# STM32F7.net
KiCad netlist of a schematic drawn in Altium Designer
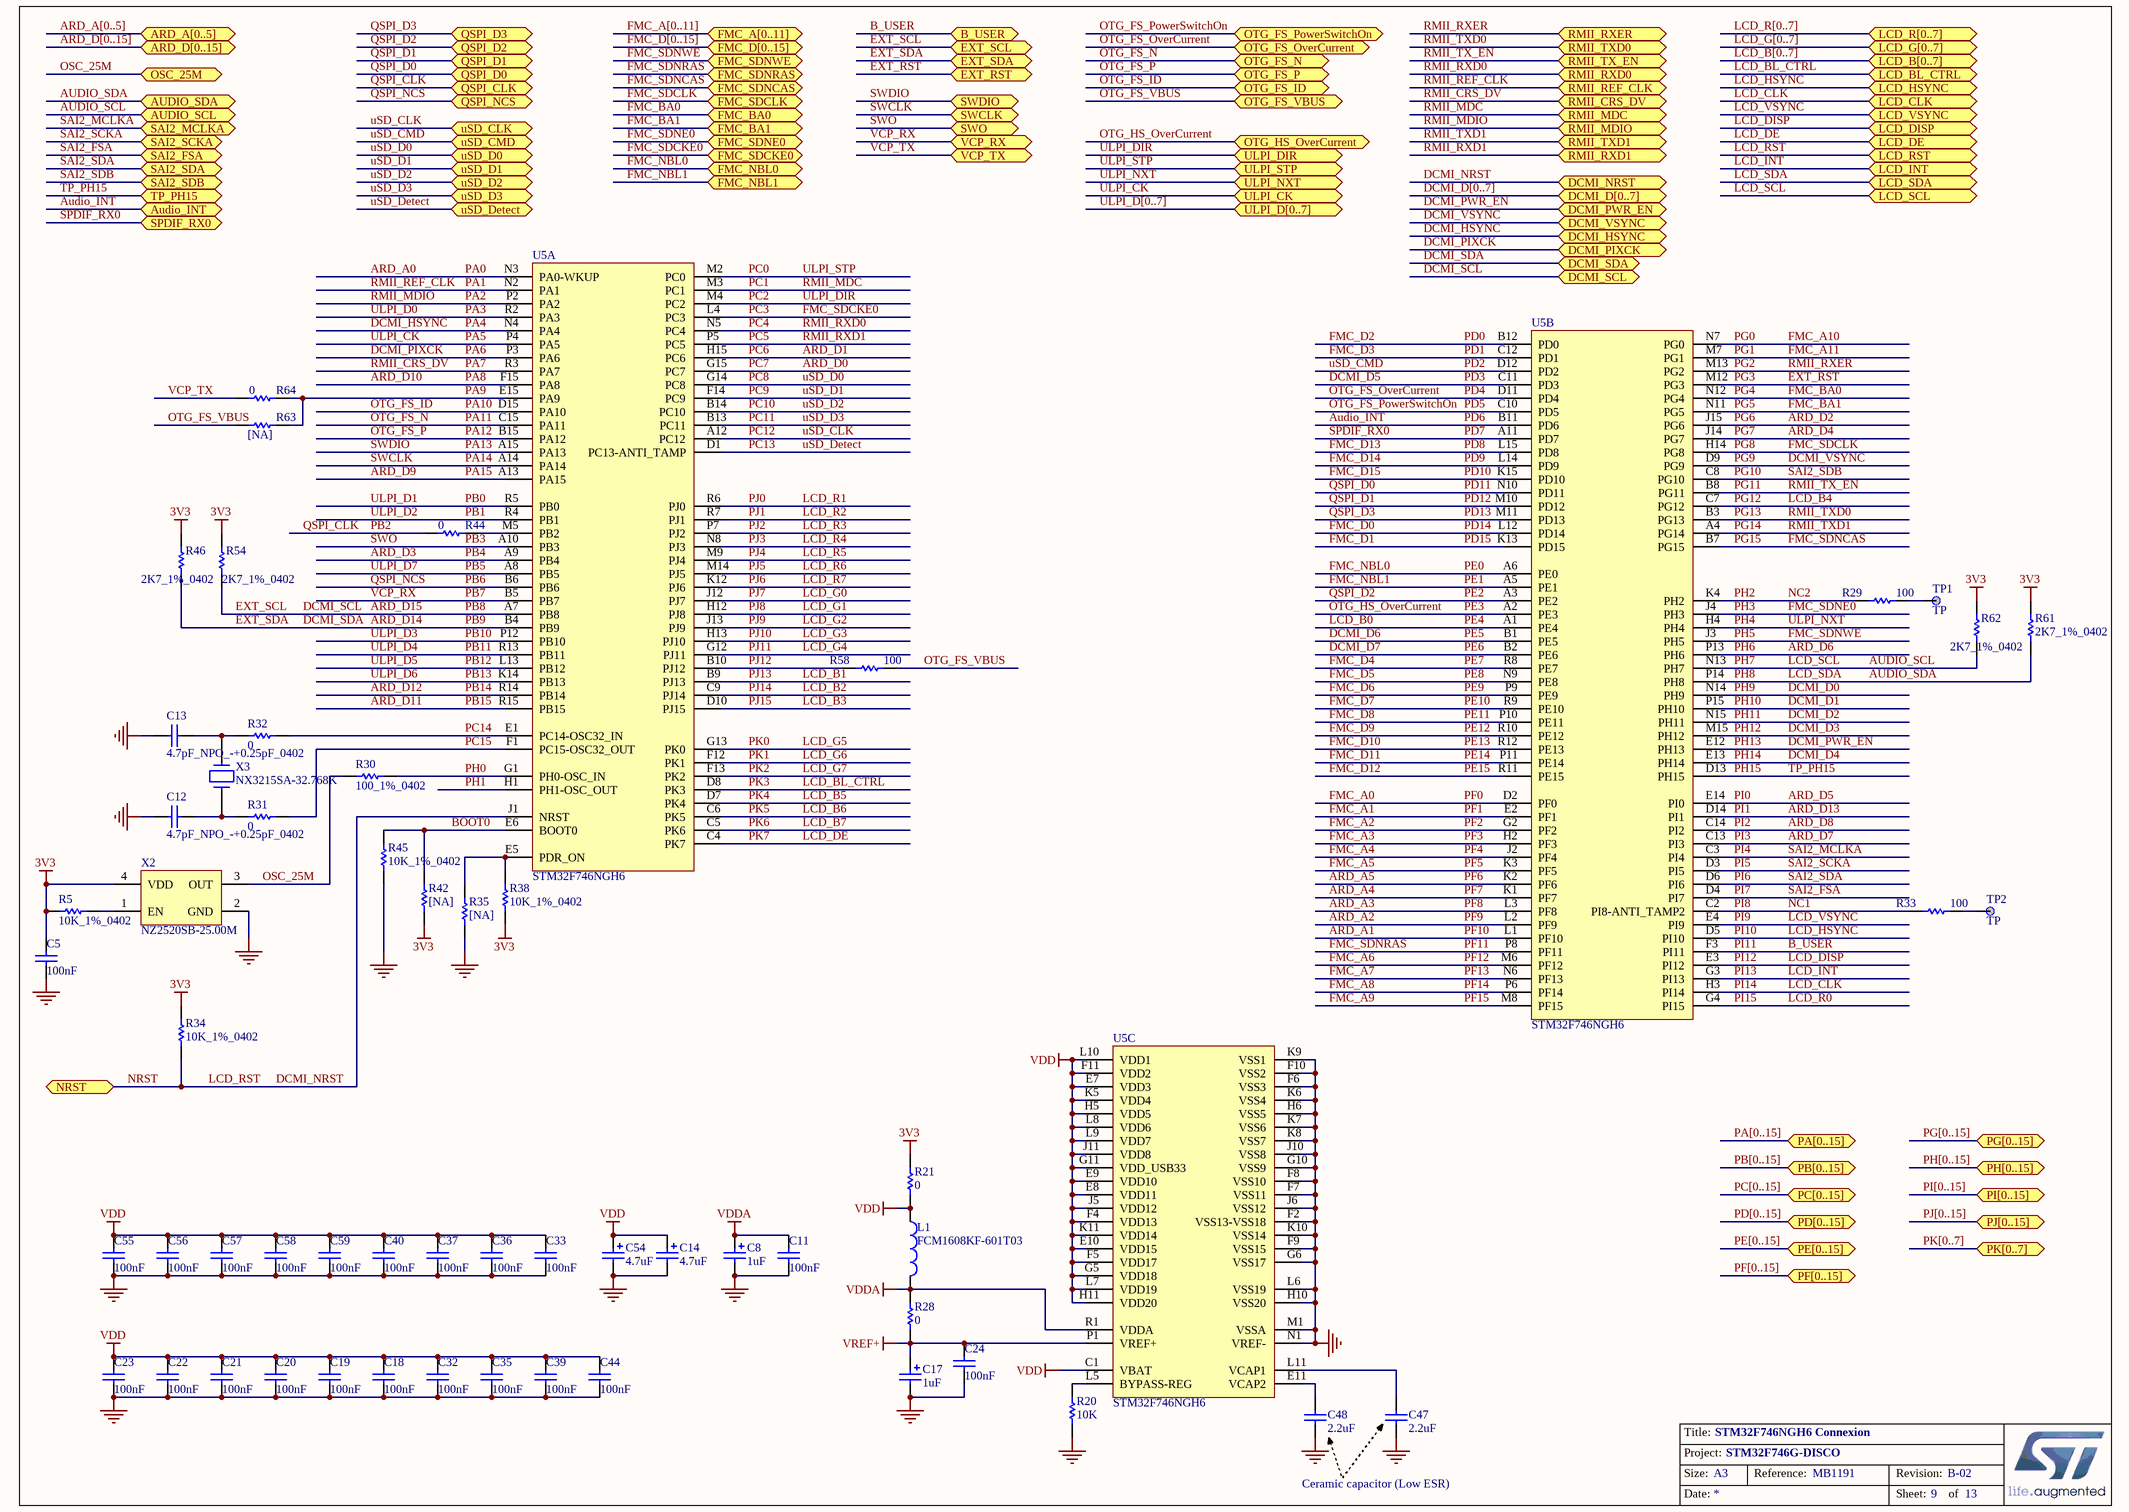
[diagram p0: STM32F7.SchDoc]

(export (version "E")
  (design (tool "Eeschema 10.0.6"))
  (components
    (comp (ref "C5")
      (value "100nF")
      (footprint "0402C")
      (description "Capacitor,100nF,16V,X7R,10%,0402,YAGEO")
      (libsource (lib "MCD_TOOLS") (part "Cap_100nF_X7R_10%_0402"))
    )
    (comp (ref "C8")
      (value "1uF")
      (footprint "TAN-A")
      (description "Polarized Capacitor,1uF,16V,10%,typeA,AVX")
      (libsource (lib "MCD_TOOLS") (part "Cap_1uF_POL_10%_TANA"))
    )
    (comp (ref "C11")
      (value "100nF")
      (footprint "0402C")
      (description "Capacitor,100nF,16V,X7R,10%,0402,YAGEO")
      (libsource (lib "MCD_TOOLS") (part "Cap_100nF_X7R_10%_0402"))
    )
    (comp (ref "C12")
      (value "4.7pF_NPO_-+0.25pF_0402")
      (footprint "0402C")
      (description "Capacitor, 4.7pF, 50V, NPO, -+0.25pF, 0402, YAGEO")
      (libsource (lib "MCD_TOOLS") (part "Cap_4.7pF_NPO_-+0.25pF_0402"))
    )
    (comp (ref "C13")
      (value "4.7pF_NPO_-+0.25pF_0402")
      (footprint "0402C")
      (description "Capacitor, 4.7pF, 50V, NPO, -+0.25pF, 0402, YAGEO")
      (libsource (lib "MCD_TOOLS") (part "Cap_4.7pF_NPO_-+0.25pF_0402"))
    )
    (comp (ref "C14")
      (value "4.7uF")
      (footprint "TAN-A")
      (description "Polarized Capacitor,4.7uF,16V,10%,typeA,AVX")
      (libsource (lib "MCD_TOOLS") (part "Cap_4.7uF_POL_10%_TANA"))
    )
    (comp (ref "C17")
      (value "1uF")
      (footprint "TAN-A")
      (description "Polarized Capacitor,1uF,16V,10%,typeA,AVX")
      (libsource (lib "MCD_TOOLS") (part "Cap_1uF_POL_10%_TANA"))
    )
    (comp (ref "C18")
      (value "100nF")
      (footprint "0402C")
      (description "Capacitor,100nF,16V,X7R,10%,0402,YAGEO")
      (libsource (lib "MCD_TOOLS") (part "Cap_100nF_X7R_10%_0402"))
    )
    (comp (ref "C19")
      (value "100nF")
      (footprint "0402C")
      (description "Capacitor,100nF,16V,X7R,10%,0402,YAGEO")
      (libsource (lib "MCD_TOOLS") (part "Cap_100nF_X7R_10%_0402"))
    )
    (comp (ref "C20")
      (value "100nF")
      (footprint "0402C")
      (description "Capacitor,100nF,16V,X7R,10%,0402,YAGEO")
      (libsource (lib "MCD_TOOLS") (part "Cap_100nF_X7R_10%_0402"))
    )
    (comp (ref "C21")
      (value "100nF")
      (footprint "0402C")
      (description "Capacitor,100nF,16V,X7R,10%,0402,YAGEO")
      (libsource (lib "MCD_TOOLS") (part "Cap_100nF_X7R_10%_0402"))
    )
    (comp (ref "C22")
      (value "100nF")
      (footprint "0402C")
      (description "Capacitor,100nF,16V,X7R,10%,0402,YAGEO")
      (libsource (lib "MCD_TOOLS") (part "Cap_100nF_X7R_10%_0402"))
    )
    (comp (ref "C23")
      (value "100nF")
      (footprint "0402C")
      (description "Capacitor,100nF,16V,X7R,10%,0402,YAGEO")
      (libsource (lib "MCD_TOOLS") (part "Cap_100nF_X7R_10%_0402"))
    )
    (comp (ref "C24")
      (value "100nF")
      (footprint "0402C")
      (description "Capacitor,100nF,16V,X7R,10%,0402,YAGEO")
      (libsource (lib "MCD_TOOLS") (part "Cap_100nF_X7R_10%_0402"))
    )
    (comp (ref "C32")
      (value "100nF")
      (footprint "0402C")
      (description "Capacitor,100nF,16V,X7R,10%,0402,YAGEO")
      (libsource (lib "MCD_TOOLS") (part "Cap_100nF_X7R_10%_0402"))
    )
    (comp (ref "C33")
      (value "100nF")
      (footprint "0402C")
      (description "Capacitor,100nF,16V,X7R,10%,0402,YAGEO")
      (libsource (lib "MCD_TOOLS") (part "Cap_100nF_X7R_10%_0402"))
    )
    (comp (ref "C35")
      (value "100nF")
      (footprint "0402C")
      (description "Capacitor,100nF,16V,X7R,10%,0402,YAGEO")
      (libsource (lib "MCD_TOOLS") (part "Cap_100nF_X7R_10%_0402"))
    )
    (comp (ref "C36")
      (value "100nF")
      (footprint "0402C")
      (description "Capacitor,100nF,16V,X7R,10%,0402,YAGEO")
      (libsource (lib "MCD_TOOLS") (part "Cap_100nF_X7R_10%_0402"))
    )
    (comp (ref "C37")
      (value "100nF")
      (footprint "0402C")
      (description "Capacitor,100nF,16V,X7R,10%,0402,YAGEO")
      (libsource (lib "MCD_TOOLS") (part "Cap_100nF_X7R_10%_0402"))
    )
    (comp (ref "C39")
      (value "100nF")
      (footprint "0402C")
      (description "Capacitor,100nF,16V,X7R,10%,0402,YAGEO")
      (libsource (lib "MCD_TOOLS") (part "Cap_100nF_X7R_10%_0402"))
    )
    (comp (ref "C40")
      (value "100nF")
      (footprint "0402C")
      (description "Capacitor,100nF,16V,X7R,10%,0402,YAGEO")
      (libsource (lib "MCD_TOOLS") (part "Cap_100nF_X7R_10%_0402"))
    )
    (comp (ref "C44")
      (value "100nF")
      (footprint "0402C")
      (description "Capacitor,100nF,16V,X7R,10%,0402,YAGEO")
      (libsource (lib "MCD_TOOLS") (part "Cap_100nF_X7R_10%_0402"))
    )
    (comp (ref "C47")
      (value "2.2uF")
      (footprint "1206C")
      (description "Capacitor,2.2uF,16V, X7R,10%,1206,YAGEO")
      (libsource (lib "MCD_TOOLS") (part "Cap_2.2uF_X7R_10%_1206"))
    )
    (comp (ref "C48")
      (value "2.2uF")
      (footprint "1206C")
      (description "Capacitor,2.2uF,16V, X7R,10%,1206,YAGEO")
      (libsource (lib "MCD_TOOLS") (part "Cap_2.2uF_X7R_10%_1206"))
    )
    (comp (ref "C54")
      (value "4.7uF")
      (footprint "TAN-A")
      (description "Polarized Capacitor,4.7uF,16V,10%,typeA,AVX")
      (libsource (lib "MCD_TOOLS") (part "Cap_4.7uF_POL_10%_TANA"))
    )
    (comp (ref "C55")
      (value "100nF")
      (footprint "0402C")
      (description "Capacitor,100nF,16V,X7R,10%,0402,YAGEO")
      (libsource (lib "MCD_TOOLS") (part "Cap_100nF_X7R_10%_0402"))
    )
    (comp (ref "C56")
      (value "100nF")
      (footprint "0402C")
      (description "Capacitor,100nF,16V,X7R,10%,0402,YAGEO")
      (libsource (lib "MCD_TOOLS") (part "Cap_100nF_X7R_10%_0402"))
    )
    (comp (ref "C57")
      (value "100nF")
      (footprint "0402C")
      (description "Capacitor,100nF,16V,X7R,10%,0402,YAGEO")
      (libsource (lib "MCD_TOOLS") (part "Cap_100nF_X7R_10%_0402"))
    )
    (comp (ref "C58")
      (value "100nF")
      (footprint "0402C")
      (description "Capacitor,100nF,16V,X7R,10%,0402,YAGEO")
      (libsource (lib "MCD_TOOLS") (part "Cap_100nF_X7R_10%_0402"))
    )
    (comp (ref "C59")
      (value "100nF")
      (footprint "0402C")
      (description "Capacitor,100nF,16V,X7R,10%,0402,YAGEO")
      (libsource (lib "MCD_TOOLS") (part "Cap_100nF_X7R_10%_0402"))
    )
    (comp (ref "L1")
      (value "FCM1608KF-601T03")
      (footprint "0603L")
      (description "Bead,600R,350mA,0603,FCM1608KF-601T03,Tai-tech")
      (libsource (lib "MCD_TOOLS") (part "BEAD_600R_350MA_0603"))
    )
    (comp (ref "R5")
      (value "10K_1%_0402")
      (footprint "0402R")
      (description "Resistor,10K,0402,1%,YAGEO")
      (libsource (lib "MCD_TOOLS") (part "Res_10K_1%_0402"))
    )
    (comp (ref "R20")
      (value "10K")
      (footprint "0402R")
      (description "Resistor,10K,0402,1%,YAGEO")
      (libsource (lib "MCD_TOOLS") (part "Res_10K_1%_0402"))
    )
    (comp (ref "R21")
      (value "0")
      (footprint "0603R-GS")
      (description "Resistor,0,0603,5%,YAGEO")
      (libsource (lib "MCD_TOOLS") (part "Res_0_5%_0603"))
    )
    (comp (ref "R28")
      (value "0")
      (footprint "0603R-GS")
      (description "Resistor,0,0603,5%,YAGEO")
      (libsource (lib "MCD_TOOLS") (part "Res_0_5%_0603"))
    )
    (comp (ref "R29")
      (value "100")
      (footprint "0402R")
      (description "Resistor,100,0402,1%,YAGEO")
      (libsource (lib "MCD_TOOLS") (part "Res_100_1%_0402"))
    )
    (comp (ref "R30")
      (value "100_1%_0402")
      (footprint "0402R")
      (description "Resistor,100,0402,1%,YAGEO")
      (libsource (lib "MCD_TOOLS") (part "Res_100_1%_0402"))
    )
    (comp (ref "R31")
      (value "0")
      (footprint "0402R")
      (description "Resistor,0,0402,5%,YAGEO")
      (libsource (lib "MCD_TOOLS") (part "Res_0_5%_0402"))
    )
    (comp (ref "R32")
      (value "0")
      (footprint "0402R")
      (description "Resistor,0,0402,5%,YAGEO")
      (libsource (lib "MCD_TOOLS") (part "Res_0_5%_0402"))
    )
    (comp (ref "R33")
      (value "100")
      (footprint "0402R")
      (description "Resistor,100,0402,1%,YAGEO")
      (libsource (lib "MCD_TOOLS") (part "Res_100_1%_0402"))
    )
    (comp (ref "R34")
      (value "10K_1%_0402")
      (footprint "0402R")
      (description "Resistor,10K,0402,1%,YAGEO")
      (libsource (lib "MCD_TOOLS") (part "Res_10K_1%_0402"))
    )
    (comp (ref "R35")
      (value "[NA]")
      (footprint "0402R")
      (description "Resistor,[NA],0402")
      (libsource (lib "MCD_TOOLS") (part "Res_NA_0402"))
    )
    (comp (ref "R38")
      (value "10K_1%_0402")
      (footprint "0402R")
      (description "Resistor,10K,0402,1%,YAGEO")
      (libsource (lib "MCD_TOOLS") (part "Res_10K_1%_0402"))
    )
    (comp (ref "R42")
      (value "[NA]")
      (footprint "0402R")
      (description "Resistor,[NA],0402")
      (libsource (lib "MCD_TOOLS") (part "Res_NA_0402"))
    )
    (comp (ref "R44")
      (value "0")
      (footprint "0402R")
      (description "Resistor,0,0402,5%,YAGEO")
      (libsource (lib "MCD_TOOLS") (part "Res_0_5%_0402"))
    )
    (comp (ref "R45")
      (value "10K_1%_0402")
      (footprint "0402R")
      (description "Resistor,10K,0402,1%,YAGEO")
      (libsource (lib "MCD_TOOLS") (part "Res_10K_1%_0402"))
    )
    (comp (ref "R46")
      (value "2K7_1%_0402")
      (footprint "0402R")
      (description "Resistor,2K7,0402,1%,YAGEO")
      (libsource (lib "MCD_TOOLS") (part "Res_2K7_1%_0402"))
    )
    (comp (ref "R54")
      (value "2K7_1%_0402")
      (footprint "0402R")
      (description "Resistor,2K7,0402,1%,YAGEO")
      (libsource (lib "MCD_TOOLS") (part "Res_2K7_1%_0402"))
    )
    (comp (ref "R58")
      (value "100")
      (footprint "0402R")
      (description "Resistor,100,0402,1%,YAGEO")
      (libsource (lib "MCD_TOOLS") (part "Res_100_1%_0402"))
    )
    (comp (ref "R61")
      (value "2K7_1%_0402")
      (footprint "0402R")
      (description "Resistor,2K7,0402,1%,YAGEO")
      (libsource (lib "MCD_TOOLS") (part "Res_2K7_1%_0402"))
    )
    (comp (ref "R62")
      (value "2K7_1%_0402")
      (footprint "0402R")
      (description "Resistor,2K7,0402,1%,YAGEO")
      (libsource (lib "MCD_TOOLS") (part "Res_2K7_1%_0402"))
    )
    (comp (ref "R63")
      (value "[NA]")
      (footprint "0402R")
      (description "Resistor,[NA],0402")
      (libsource (lib "MCD_TOOLS") (part "Res_NA_0402"))
    )
    (comp (ref "R64")
      (value "0")
      (footprint "0402R")
      (description "Resistor,0,0402,5%,YAGEO")
      (libsource (lib "MCD_TOOLS") (part "Res_0_5%_0402"))
    )
    (comp (ref "TP1")
      (value "TP")
      (footprint "SMDTEST-1MM")
      (description "Test Point CMS")
      (libsource (lib "MCD_TOOLS") (part "TP"))
    )
    (comp (ref "TP2")
      (value "TP")
      (footprint "SMDTEST-1MM")
      (description "Test Point CMS")
      (libsource (lib "MCD_TOOLS") (part "TP"))
    )
    (comp (ref "U5")
      (value "STM32F746NGH6")
      (footprint "BGA216_0R8_13X13_SKT")
      (description "STM32F746NGH6 (STM32F7 Birdie) TBGA216")
      (libsource (lib "MCD_TOOLS") (part "STM32F746NGH6U"))
    )
    (comp (ref "X2")
      (value "NZ2520SB-25.00M")
      (footprint "OSC_4SM_2R5X2R0")
      (description "Oscillator 25.00Mhz, -+50PPM, 3.3V, Temp -55 to +125°C")
      (libsource (lib "MCD_TOOLS") (part "OSC_25M_NZ2520SB"))
    )
    (comp (ref "X3")
      (value "NX3215SA-32.768K")
      (footprint "XTAL_2SM_3R2X1R5")
      (description "Crystal 32.768kHz, 6pF, -+20PPM, NDK only for ST, Type NX3215SA,  NDK Spec EXS00A-MU00525")
      (libsource (lib "MCD_TOOLS") (part "XTAL_32K_NX3215SA"))
    )
  )
  (nets
    (net (code "1") (name "/ARD_A0") (class "Default")
      (node (ref "U5") (pin "N3") (pinfunction "PA0-WKUP_N3") (pintype "passive"))
    )
    (net (code "2") (name "/ARD_A1") (class "Default")
      (node (ref "U5") (pin "L1") (pinfunction "PF10_L1") (pintype "passive"))
    )
    (net (code "3") (name "/ARD_A2") (class "Default")
      (node (ref "U5") (pin "L2") (pinfunction "PF9_L2") (pintype "passive"))
    )
    (net (code "4") (name "/ARD_A3") (class "Default")
      (node (ref "U5") (pin "L3") (pinfunction "PF8_L3") (pintype "passive"))
    )
    (net (code "5") (name "/ARD_A4") (class "Default")
      (node (ref "U5") (pin "K1") (pinfunction "PF7_K1") (pintype "passive"))
    )
    (net (code "6") (name "/ARD_A5") (class "Default")
      (node (ref "U5") (pin "K2") (pinfunction "PF6_K2") (pintype "passive"))
    )
    (net (code "8") (name "/ARD_D0") (class "Default")
      (node (ref "U5") (pin "G15") (pinfunction "PC7_G15") (pintype "passive"))
    )
    (net (code "9") (name "/ARD_D1") (class "Default")
      (node (ref "U5") (pin "H15") (pinfunction "PC6_H15") (pintype "passive"))
    )
    (net (code "10") (name "/ARD_D2") (class "Default")
      (node (ref "U5") (pin "J15") (pinfunction "PG6_J15") (pintype "passive"))
    )
    (net (code "11") (name "/ARD_D3") (class "Default")
      (node (ref "U5") (pin "A9") (pinfunction "PB4_A9") (pintype "passive"))
    )
    (net (code "12") (name "/ARD_D4") (class "Default")
      (node (ref "U5") (pin "J14") (pinfunction "PG7_J14") (pintype "passive"))
    )
    (net (code "13") (name "/ARD_D5") (class "Default")
      (node (ref "U5") (pin "E14") (pinfunction "PI0_E14") (pintype "passive"))
    )
    (net (code "14") (name "/ARD_D6") (class "Default")
      (node (ref "U5") (pin "P13") (pinfunction "PH6_P13") (pintype "passive"))
    )
    (net (code "15") (name "/ARD_D7") (class "Default")
      (node (ref "U5") (pin "C13") (pinfunction "PI3_C13") (pintype "passive"))
    )
    (net (code "16") (name "/ARD_D8") (class "Default")
      (node (ref "U5") (pin "C14") (pinfunction "PI2_C14") (pintype "passive"))
    )
    (net (code "17") (name "/ARD_D9") (class "Default")
      (node (ref "U5") (pin "A13") (pinfunction "PA15_A13") (pintype "passive"))
    )
    (net (code "18") (name "/ARD_D10") (class "Default")
      (node (ref "U5") (pin "F15") (pinfunction "PA8_F15") (pintype "passive"))
    )
    (net (code "19") (name "/ARD_D11") (class "Default")
      (node (ref "U5") (pin "R15") (pinfunction "PB15_R15") (pintype "passive"))
    )
    (net (code "20") (name "/ARD_D12") (class "Default")
      (node (ref "U5") (pin "R14") (pinfunction "PB14_R14") (pintype "passive"))
    )
    (net (code "21") (name "/ARD_D13") (class "Default")
      (node (ref "U5") (pin "D14") (pinfunction "PI1_D14") (pintype "passive"))
    )
    (net (code "22") (name "/ARD_D14") (class "Default")
      (node (ref "R46") (pin "1") (pinfunction "1_1") (pintype "passive"))
      (node (ref "U5") (pin "B4") (pinfunction "PB9_B4") (pintype "passive"))
    )
    (net (code "23") (name "/ARD_D15") (class "Default")
      (node (ref "R54") (pin "1") (pinfunction "1_1") (pintype "passive"))
      (node (ref "U5") (pin "A7") (pinfunction "PB8_A7") (pintype "passive"))
    )
    (net (code "25") (name "/BOOT0") (class "Default")
      (node (ref "R42") (pin "2") (pinfunction "2_2") (pintype "passive"))
      (node (ref "R45") (pin "2") (pinfunction "2_2") (pintype "passive"))
      (node (ref "U5") (pin "E6") (pinfunction "BOOT0_E6") (pintype "passive"))
    )
    (net (code "26") (name "/DCMI_D0") (class "Default")
      (node (ref "U5") (pin "N14") (pinfunction "PH9_N14") (pintype "passive"))
    )
    (net (code "27") (name "/DCMI_D1") (class "Default")
      (node (ref "U5") (pin "P15") (pinfunction "PH10_P15") (pintype "passive"))
    )
    (net (code "28") (name "/DCMI_D2") (class "Default")
      (node (ref "U5") (pin "N15") (pinfunction "PH11_N15") (pintype "passive"))
    )
    (net (code "29") (name "/DCMI_D3") (class "Default")
      (node (ref "U5") (pin "M15") (pinfunction "PH12_M15") (pintype "passive"))
    )
    (net (code "30") (name "/DCMI_D4") (class "Default")
      (node (ref "U5") (pin "E13") (pinfunction "PH14_E13") (pintype "passive"))
    )
    (net (code "31") (name "/DCMI_D5") (class "Default")
      (node (ref "U5") (pin "C11") (pinfunction "PD3_C11") (pintype "passive"))
    )
    (net (code "32") (name "/DCMI_D6") (class "Default")
      (node (ref "U5") (pin "B1") (pinfunction "PE5_B1") (pintype "passive"))
    )
    (net (code "33") (name "/DCMI_D7") (class "Default")
      (node (ref "U5") (pin "B2") (pinfunction "PE6_B2") (pintype "passive"))
    )
    (net (code "35") (name "/DCMI_NRST") (class "Default")
      (node (ref "R34") (pin "1") (pinfunction "1_1") (pintype "passive"))
      (node (ref "U5") (pin "J1") (pinfunction "NRST_J1") (pintype "passive"))
    )
    (net (code "36") (name "/FMC_A0") (class "Default")
      (node (ref "U5") (pin "D2") (pinfunction "PF0_D2") (pintype "passive"))
    )
    (net (code "37") (name "/FMC_A1") (class "Default")
      (node (ref "U5") (pin "E2") (pinfunction "PF1_E2") (pintype "passive"))
    )
    (net (code "38") (name "/FMC_A2") (class "Default")
      (node (ref "U5") (pin "G2") (pinfunction "PF2_G2") (pintype "passive"))
    )
    (net (code "39") (name "/FMC_A3") (class "Default")
      (node (ref "U5") (pin "H2") (pinfunction "PF3_H2") (pintype "passive"))
    )
    (net (code "40") (name "/FMC_A4") (class "Default")
      (node (ref "U5") (pin "J2") (pinfunction "PF4_J2") (pintype "passive"))
    )
    (net (code "41") (name "/FMC_A5") (class "Default")
      (node (ref "U5") (pin "K3") (pinfunction "PF5_K3") (pintype "passive"))
    )
    (net (code "42") (name "/FMC_A6") (class "Default")
      (node (ref "U5") (pin "M6") (pinfunction "PF12_M6") (pintype "passive"))
    )
    (net (code "43") (name "/FMC_A7") (class "Default")
      (node (ref "U5") (pin "N6") (pinfunction "PF13_N6") (pintype "passive"))
    )
    (net (code "44") (name "/FMC_A8") (class "Default")
      (node (ref "U5") (pin "P6") (pinfunction "PF14_P6") (pintype "passive"))
    )
    (net (code "45") (name "/FMC_A9") (class "Default")
      (node (ref "U5") (pin "M8") (pinfunction "PF15_M8") (pintype "passive"))
    )
    (net (code "46") (name "/FMC_A10") (class "Default")
      (node (ref "U5") (pin "N7") (pinfunction "PG0_N7") (pintype "passive"))
    )
    (net (code "47") (name "/FMC_A11") (class "Default")
      (node (ref "U5") (pin "M7") (pinfunction "PG1_M7") (pintype "passive"))
    )
    (net (code "49") (name "/FMC_D0") (class "Default")
      (node (ref "U5") (pin "L12") (pinfunction "PD14_L12") (pintype "passive"))
    )
    (net (code "50") (name "/FMC_D1") (class "Default")
      (node (ref "U5") (pin "K13") (pinfunction "PD15_K13") (pintype "passive"))
    )
    (net (code "51") (name "/FMC_D2") (class "Default")
      (node (ref "U5") (pin "B12") (pinfunction "PD0_B12") (pintype "passive"))
    )
    (net (code "52") (name "/FMC_D3") (class "Default")
      (node (ref "U5") (pin "C12") (pinfunction "PD1_C12") (pintype "passive"))
    )
    (net (code "53") (name "/FMC_D4") (class "Default")
      (node (ref "U5") (pin "R8") (pinfunction "PE7_R8") (pintype "passive"))
    )
    (net (code "54") (name "/FMC_D5") (class "Default")
      (node (ref "U5") (pin "N9") (pinfunction "PE8_N9") (pintype "passive"))
    )
    (net (code "55") (name "/FMC_D6") (class "Default")
      (node (ref "U5") (pin "P9") (pinfunction "PE9_P9") (pintype "passive"))
    )
    (net (code "56") (name "/FMC_D7") (class "Default")
      (node (ref "U5") (pin "R9") (pinfunction "PE10_R9") (pintype "passive"))
    )
    (net (code "57") (name "/FMC_D8") (class "Default")
      (node (ref "U5") (pin "P10") (pinfunction "PE11_P10") (pintype "passive"))
    )
    (net (code "58") (name "/FMC_D9") (class "Default")
      (node (ref "U5") (pin "R10") (pinfunction "PE12_R10") (pintype "passive"))
    )
    (net (code "59") (name "/FMC_D10") (class "Default")
      (node (ref "U5") (pin "R12") (pinfunction "PE13_R12") (pintype "passive"))
    )
    (net (code "60") (name "/FMC_D11") (class "Default")
      (node (ref "U5") (pin "P11") (pinfunction "PE14_P11") (pintype "passive"))
    )
    (net (code "61") (name "/FMC_D12") (class "Default")
      (node (ref "U5") (pin "R11") (pinfunction "PE15_R11") (pintype "passive"))
    )
    (net (code "62") (name "/FMC_D13") (class "Default")
      (node (ref "U5") (pin "L15") (pinfunction "PD8_L15") (pintype "passive"))
    )
    (net (code "63") (name "/FMC_D14") (class "Default")
      (node (ref "U5") (pin "L14") (pinfunction "PD9_L14") (pintype "passive"))
    )
    (net (code "64") (name "/FMC_D15") (class "Default")
      (node (ref "U5") (pin "K15") (pinfunction "PD10_K15") (pintype "passive"))
    )
    (net (code "66") (name "/LCD_B0") (class "Default")
      (node (ref "U5") (pin "A1") (pinfunction "PE4_A1") (pintype "passive"))
    )
    (net (code "67") (name "/LCD_B1") (class "Default")
      (node (ref "U5") (pin "B9") (pinfunction "PJ13_B9") (pintype "passive"))
    )
    (net (code "68") (name "/LCD_B2") (class "Default")
      (node (ref "U5") (pin "C9") (pinfunction "PJ14_C9") (pintype "passive"))
    )
    (net (code "69") (name "/LCD_B3") (class "Default")
      (node (ref "U5") (pin "D10") (pinfunction "PJ15_D10") (pintype "passive"))
    )
    (net (code "70") (name "/LCD_B4") (class "Default")
      (node (ref "U5") (pin "C7") (pinfunction "PG12_C7") (pintype "passive"))
    )
    (net (code "71") (name "/LCD_B5") (class "Default")
      (node (ref "U5") (pin "D7") (pinfunction "PK4_D7") (pintype "passive"))
    )
    (net (code "72") (name "/LCD_B6") (class "Default")
      (node (ref "U5") (pin "C6") (pinfunction "PK5_C6") (pintype "passive"))
    )
    (net (code "73") (name "/LCD_B7") (class "Default")
      (node (ref "U5") (pin "C5") (pinfunction "PK6_C5") (pintype "passive"))
    )
    (net (code "75") (name "/LCD_G0") (class "Default")
      (node (ref "U5") (pin "J12") (pinfunction "PJ7_J12") (pintype "passive"))
    )
    (net (code "76") (name "/LCD_G1") (class "Default")
      (node (ref "U5") (pin "H12") (pinfunction "PJ8_H12") (pintype "passive"))
    )
    (net (code "77") (name "/LCD_G2") (class "Default")
      (node (ref "U5") (pin "J13") (pinfunction "PJ9_J13") (pintype "passive"))
    )
    (net (code "78") (name "/LCD_G3") (class "Default")
      (node (ref "U5") (pin "H13") (pinfunction "PJ10_H13") (pintype "passive"))
    )
    (net (code "79") (name "/LCD_G4") (class "Default")
      (node (ref "U5") (pin "G12") (pinfunction "PJ11_G12") (pintype "passive"))
    )
    (net (code "80") (name "/LCD_G5") (class "Default")
      (node (ref "U5") (pin "G13") (pinfunction "PK0_G13") (pintype "passive"))
    )
    (net (code "81") (name "/LCD_G6") (class "Default")
      (node (ref "U5") (pin "F12") (pinfunction "PK1_F12") (pintype "passive"))
    )
    (net (code "82") (name "/LCD_G7") (class "Default")
      (node (ref "U5") (pin "F13") (pinfunction "PK2_F13") (pintype "passive"))
    )
    (net (code "84") (name "/LCD_R0") (class "Default")
      (node (ref "U5") (pin "G4") (pinfunction "PI15_G4") (pintype "passive"))
    )
    (net (code "85") (name "/LCD_R1") (class "Default")
      (node (ref "U5") (pin "R6") (pinfunction "PJ0_R6") (pintype "passive"))
    )
    (net (code "86") (name "/LCD_R2") (class "Default")
      (node (ref "U5") (pin "R7") (pinfunction "PJ1_R7") (pintype "passive"))
    )
    (net (code "87") (name "/LCD_R3") (class "Default")
      (node (ref "U5") (pin "P7") (pinfunction "PJ2_P7") (pintype "passive"))
    )
    (net (code "88") (name "/LCD_R4") (class "Default")
      (node (ref "U5") (pin "N8") (pinfunction "PJ3_N8") (pintype "passive"))
    )
    (net (code "89") (name "/LCD_R5") (class "Default")
      (node (ref "U5") (pin "M9") (pinfunction "PJ4_M9") (pintype "passive"))
    )
    (net (code "90") (name "/LCD_R6") (class "Default")
      (node (ref "U5") (pin "M14") (pinfunction "PJ5_M14") (pintype "passive"))
    )
    (net (code "91") (name "/LCD_R7") (class "Default")
      (node (ref "U5") (pin "K12") (pinfunction "PJ6_K12") (pintype "passive"))
    )
    (net (code "93") (name "/OSC_25M") (class "Default")
      (node (ref "R30") (pin "1") (pinfunction "1_1") (pintype "passive"))
      (node (ref "X2") (pin "3") (pinfunction "OUT_3") (pintype "passive"))
    )
    (net (code "94") (name "/OTG_FS_VBUS") (class "Default")
      (node (ref "R58") (pin "2") (pinfunction "2_2") (pintype "passive"))
      (node (ref "R63") (pin "1") (pinfunction "1_1") (pintype "passive"))
    )
    (net (code "95") (name "/PA1") (class "Default")
      (node (ref "U5") (pin "N2") (pinfunction "PA1_N2") (pintype "passive"))
    )
    (net (code "96") (name "/PA2") (class "Default")
      (node (ref "U5") (pin "P2") (pinfunction "PA2_P2") (pintype "passive"))
    )
    (net (code "97") (name "/PA4") (class "Default")
      (node (ref "U5") (pin "N4") (pinfunction "PA4_N4") (pintype "passive"))
    )
    (net (code "98") (name "/PA5") (class "Default")
      (node (ref "U5") (pin "P4") (pinfunction "PA5_P4") (pintype "passive"))
    )
    (net (code "99") (name "/PA6") (class "Default")
      (node (ref "U5") (pin "P3") (pinfunction "PA6_P3") (pintype "passive"))
    )
    (net (code "100") (name "/PA7") (class "Default")
      (node (ref "U5") (pin "R3") (pinfunction "PA7_R3") (pintype "passive"))
    )
    (net (code "101") (name "/PA9") (class "Default")
      (node (ref "R63") (pin "2") (pinfunction "2_2") (pintype "passive"))
      (node (ref "R64") (pin "2") (pinfunction "2_2") (pintype "passive"))
      (node (ref "U5") (pin "E15") (pinfunction "PA9_E15") (pintype "passive"))
    )
    (net (code "102") (name "/PA10") (class "Default")
      (node (ref "U5") (pin "D15") (pinfunction "PA10_D15") (pintype "passive"))
    )
    (net (code "103") (name "/PA11") (class "Default")
      (node (ref "U5") (pin "C15") (pinfunction "PA11_C15") (pintype "passive"))
    )
    (net (code "104") (name "/PA12") (class "Default")
      (node (ref "U5") (pin "B15") (pinfunction "PA12_B15") (pintype "passive"))
    )
    (net (code "105") (name "/PA13") (class "Default")
      (node (ref "U5") (pin "A15") (pinfunction "PA13_A15") (pintype "passive"))
    )
    (net (code "106") (name "/PA14") (class "Default")
      (node (ref "U5") (pin "A14") (pinfunction "PA14_A14") (pintype "passive"))
    )
    (net (code "108") (name "/PB2") (class "Default")
      (node (ref "R44") (pin "1") (pinfunction "1_1") (pintype "passive"))
    )
    (net (code "109") (name "/PB3") (class "Default")
      (node (ref "U5") (pin "A10") (pinfunction "PB3_A10") (pintype "passive"))
    )
    (net (code "110") (name "/PB6") (class "Default")
      (node (ref "U5") (pin "B6") (pinfunction "PB6_B6") (pintype "passive"))
    )
    (net (code "111") (name "/PB7") (class "Default")
      (node (ref "U5") (pin "B5") (pinfunction "PB7_B5") (pintype "passive"))
    )
    (net (code "113") (name "/PC0") (class "Default")
      (node (ref "U5") (pin "M2") (pinfunction "PC0_M2") (pintype "passive"))
    )
    (net (code "114") (name "/PC1") (class "Default")
      (node (ref "U5") (pin "M3") (pinfunction "PC1_M3") (pintype "passive"))
    )
    (net (code "115") (name "/PC2") (class "Default")
      (node (ref "U5") (pin "M4") (pinfunction "PC2_M4") (pintype "passive"))
    )
    (net (code "116") (name "/PC3") (class "Default")
      (node (ref "U5") (pin "L4") (pinfunction "PC3_L4") (pintype "passive"))
    )
    (net (code "117") (name "/PC4") (class "Default")
      (node (ref "U5") (pin "N5") (pinfunction "PC4_N5") (pintype "passive"))
    )
    (net (code "118") (name "/PC5") (class "Default")
      (node (ref "U5") (pin "P5") (pinfunction "PC5_P5") (pintype "passive"))
    )
    (net (code "119") (name "/PC8") (class "Default")
      (node (ref "U5") (pin "G14") (pinfunction "PC8_G14") (pintype "passive"))
    )
    (net (code "120") (name "/PC9") (class "Default")
      (node (ref "U5") (pin "F14") (pinfunction "PC9_F14") (pintype "passive"))
    )
    (net (code "121") (name "/PC10") (class "Default")
      (node (ref "U5") (pin "B14") (pinfunction "PC10_B14") (pintype "passive"))
    )
    (net (code "122") (name "/PC11") (class "Default")
      (node (ref "U5") (pin "B13") (pinfunction "PC11_B13") (pintype "passive"))
    )
    (net (code "123") (name "/PC12") (class "Default")
      (node (ref "U5") (pin "A12") (pinfunction "PC12_A12") (pintype "passive"))
    )
    (net (code "124") (name "/PC13") (class "Default")
      (node (ref "U5") (pin "D1") (pinfunction "PC13-ANTI_TAMP_D1") (pintype "passive"))
    )
    (net (code "125") (name "/PC14") (class "Default")
      (node (ref "R32") (pin "2") (pinfunction "2_2") (pintype "passive"))
      (node (ref "U5") (pin "E1") (pinfunction "PC14-OSC32_IN_E1") (pintype "passive"))
    )
    (net (code "126") (name "/PC15") (class "Default")
      (node (ref "R31") (pin "2") (pinfunction "2_2") (pintype "passive"))
      (node (ref "U5") (pin "F1") (pinfunction "PC15-OSC32_OUT_F1") (pintype "passive"))
    )
    (net (code "128") (name "/PD2") (class "Default")
      (node (ref "U5") (pin "D12") (pinfunction "PD2_D12") (pintype "passive"))
    )
    (net (code "129") (name "/PD4") (class "Default")
      (node (ref "U5") (pin "D11") (pinfunction "PD4_D11") (pintype "passive"))
    )
    (net (code "130") (name "/PD5") (class "Default")
      (node (ref "U5") (pin "C10") (pinfunction "PD5_C10") (pintype "passive"))
    )
    (net (code "131") (name "/PD6") (class "Default")
      (node (ref "U5") (pin "B11") (pinfunction "PD6_B11") (pintype "passive"))
    )
    (net (code "132") (name "/PD7") (class "Default")
      (node (ref "U5") (pin "A11") (pinfunction "PD7_A11") (pintype "passive"))
    )
    (net (code "133") (name "/PD11") (class "Default")
      (node (ref "U5") (pin "N10") (pinfunction "PD11_N10") (pintype "passive"))
    )
    (net (code "134") (name "/PD12") (class "Default")
      (node (ref "U5") (pin "M10") (pinfunction "PD12_M10") (pintype "passive"))
    )
    (net (code "135") (name "/PD13") (class "Default")
      (node (ref "U5") (pin "M11") (pinfunction "PD13_M11") (pintype "passive"))
    )
    (net (code "137") (name "/PE0") (class "Default")
      (node (ref "U5") (pin "A6") (pinfunction "PE0_A6") (pintype "passive"))
    )
    (net (code "138") (name "/PE1") (class "Default")
      (node (ref "U5") (pin "A5") (pinfunction "PE1_A5") (pintype "passive"))
    )
    (net (code "139") (name "/PE2") (class "Default")
      (node (ref "U5") (pin "A3") (pinfunction "PE2_A3") (pintype "passive"))
    )
    (net (code "140") (name "/PE3") (class "Default")
      (node (ref "U5") (pin "A2") (pinfunction "PE3_A2") (pintype "passive"))
    )
    (net (code "142") (name "/PF11") (class "Default")
      (node (ref "U5") (pin "P8") (pinfunction "PF11_P8") (pintype "passive"))
    )
    (net (code "144") (name "/PG2") (class "Default")
      (node (ref "U5") (pin "M13") (pinfunction "PG2_M13") (pintype "passive"))
    )
    (net (code "145") (name "/PG3") (class "Default")
      (node (ref "U5") (pin "M12") (pinfunction "PG3_M12") (pintype "passive"))
    )
    (net (code "146") (name "/PG4") (class "Default")
      (node (ref "U5") (pin "N12") (pinfunction "PG4_N12") (pintype "passive"))
    )
    (net (code "147") (name "/PG5") (class "Default")
      (node (ref "U5") (pin "N11") (pinfunction "PG5_N11") (pintype "passive"))
    )
    (net (code "148") (name "/PG8") (class "Default")
      (node (ref "U5") (pin "H14") (pinfunction "PG8_H14") (pintype "passive"))
    )
    (net (code "149") (name "/PG9") (class "Default")
      (node (ref "U5") (pin "D9") (pinfunction "PG9_D9") (pintype "passive"))
    )
    (net (code "150") (name "/PG10") (class "Default")
      (node (ref "U5") (pin "C8") (pinfunction "PG10_C8") (pintype "passive"))
    )
    (net (code "151") (name "/PG11") (class "Default")
      (node (ref "U5") (pin "B8") (pinfunction "PG11_B8") (pintype "passive"))
    )
    (net (code "152") (name "/PG13") (class "Default")
      (node (ref "U5") (pin "B3") (pinfunction "PG13_B3") (pintype "passive"))
    )
    (net (code "153") (name "/PG14") (class "Default")
      (node (ref "U5") (pin "A4") (pinfunction "PG14_A4") (pintype "passive"))
    )
    (net (code "154") (name "/PG15") (class "Default")
      (node (ref "U5") (pin "B7") (pinfunction "PG15_B7") (pintype "passive"))
    )
    (net (code "156") (name "/PH0") (class "Default")
      (node (ref "R30") (pin "2") (pinfunction "2_2") (pintype "passive"))
      (node (ref "U5") (pin "G1") (pinfunction "PH0-OSC_IN_G1") (pintype "passive"))
    )
    (net (code "157") (name "/PH1") (class "Default")
      (node (ref "U5") (pin "H1") (pinfunction "PH1-OSC_OUT_H1") (pintype "passive"))
    )
    (net (code "158") (name "/PH2") (class "Default")
      (node (ref "R29") (pin "1") (pinfunction "1_1") (pintype "passive"))
      (node (ref "U5") (pin "K4") (pinfunction "PH2_K4") (pintype "passive"))
    )
    (net (code "159") (name "/PH3") (class "Default")
      (node (ref "U5") (pin "J4") (pinfunction "PH3_J4") (pintype "passive"))
    )
    (net (code "160") (name "/PH4") (class "Default")
      (node (ref "U5") (pin "H4") (pinfunction "PH4_H4") (pintype "passive"))
    )
    (net (code "161") (name "/PH5") (class "Default")
      (node (ref "U5") (pin "J3") (pinfunction "PH5_J3") (pintype "passive"))
    )
    (net (code "162") (name "/PH7") (class "Default")
      (node (ref "R62") (pin "1") (pinfunction "1_1") (pintype "passive"))
      (node (ref "U5") (pin "N13") (pinfunction "PH7_N13") (pintype "passive"))
    )
    (net (code "163") (name "/PH8") (class "Default")
      (node (ref "R61") (pin "1") (pinfunction "1_1") (pintype "passive"))
      (node (ref "U5") (pin "P14") (pinfunction "PH8_P14") (pintype "passive"))
    )
    (net (code "164") (name "/PH13") (class "Default")
      (node (ref "U5") (pin "E12") (pinfunction "PH13_E12") (pintype "passive"))
    )
    (net (code "165") (name "/PH15") (class "Default")
      (node (ref "U5") (pin "D13") (pinfunction "PH15_D13") (pintype "passive"))
    )
    (net (code "167") (name "/PI4") (class "Default")
      (node (ref "U5") (pin "C3") (pinfunction "PI4_C3") (pintype "passive"))
    )
    (net (code "168") (name "/PI5") (class "Default")
      (node (ref "U5") (pin "D3") (pinfunction "PI5_D3") (pintype "passive"))
    )
    (net (code "169") (name "/PI6") (class "Default")
      (node (ref "U5") (pin "D6") (pinfunction "PI6_D6") (pintype "passive"))
    )
    (net (code "170") (name "/PI7") (class "Default")
      (node (ref "U5") (pin "D4") (pinfunction "PI7_D4") (pintype "passive"))
    )
    (net (code "171") (name "/PI8") (class "Default")
      (node (ref "R33") (pin "1") (pinfunction "1_1") (pintype "passive"))
      (node (ref "U5") (pin "C2") (pinfunction "PI8-ANTI_TAMP2_C2") (pintype "passive"))
    )
    (net (code "172") (name "/PI9") (class "Default")
      (node (ref "U5") (pin "E4") (pinfunction "PI9_E4") (pintype "passive"))
    )
    (net (code "173") (name "/PI10") (class "Default")
      (node (ref "U5") (pin "D5") (pinfunction "PI10_D5") (pintype "passive"))
    )
    (net (code "174") (name "/PI11") (class "Default")
      (node (ref "U5") (pin "F3") (pinfunction "PI11_F3") (pintype "passive"))
    )
    (net (code "175") (name "/PI12") (class "Default")
      (node (ref "U5") (pin "E3") (pinfunction "PI12_E3") (pintype "passive"))
    )
    (net (code "176") (name "/PI13") (class "Default")
      (node (ref "U5") (pin "G3") (pinfunction "PI13_G3") (pintype "passive"))
    )
    (net (code "177") (name "/PI14") (class "Default")
      (node (ref "U5") (pin "H3") (pinfunction "PI14_H3") (pintype "passive"))
    )
    (net (code "179") (name "/PJ12") (class "Default")
      (node (ref "R58") (pin "1") (pinfunction "1_1") (pintype "passive"))
      (node (ref "U5") (pin "B10") (pinfunction "PJ12_B10") (pintype "passive"))
    )
    (net (code "181") (name "/PK3") (class "Default")
      (node (ref "U5") (pin "D8") (pinfunction "PK3_D8") (pintype "passive"))
    )
    (net (code "182") (name "/PK7") (class "Default")
      (node (ref "U5") (pin "C4") (pinfunction "PK7_C4") (pintype "passive"))
    )
    (net (code "184") (name "/ULPI_D0") (class "Default")
      (node (ref "U5") (pin "R2") (pinfunction "PA3_R2") (pintype "passive"))
    )
    (net (code "185") (name "/ULPI_D1") (class "Default")
      (node (ref "U5") (pin "R5") (pinfunction "PB0_R5") (pintype "passive"))
    )
    (net (code "186") (name "/ULPI_D2") (class "Default")
      (node (ref "U5") (pin "R4") (pinfunction "PB1_R4") (pintype "passive"))
    )
    (net (code "187") (name "/ULPI_D3") (class "Default")
      (node (ref "U5") (pin "P12") (pinfunction "PB10_P12") (pintype "passive"))
    )
    (net (code "188") (name "/ULPI_D4") (class "Default")
      (node (ref "U5") (pin "R13") (pinfunction "PB11_R13") (pintype "passive"))
    )
    (net (code "189") (name "/ULPI_D5") (class "Default")
      (node (ref "U5") (pin "L13") (pinfunction "PB12_L13") (pintype "passive"))
    )
    (net (code "190") (name "/ULPI_D6") (class "Default")
      (node (ref "U5") (pin "K14") (pinfunction "PB13_K14") (pintype "passive"))
    )
    (net (code "191") (name "/ULPI_D7") (class "Default")
      (node (ref "U5") (pin "A8") (pinfunction "PB5_A8") (pintype "passive"))
    )
    (net (code "193") (name "/VCP_TX") (class "Default")
      (node (ref "R64") (pin "1") (pinfunction "1_1") (pintype "passive"))
    )
    (net (code "194") (name "3V3") (class "Default")
      (node (ref "C5") (pin "2") (pinfunction "2_2") (pintype "passive"))
      (node (ref "R21") (pin "2") (pinfunction "2_2") (pintype "passive"))
      (node (ref "R34") (pin "2") (pinfunction "2_2") (pintype "passive"))
      (node (ref "R38") (pin "1") (pinfunction "1_1") (pintype "passive"))
      (node (ref "R42") (pin "1") (pinfunction "1_1") (pintype "passive"))
      (node (ref "R46") (pin "2") (pinfunction "2_2") (pintype "passive"))
      (node (ref "R5") (pin "1") (pinfunction "1_1") (pintype "passive"))
      (node (ref "R54") (pin "2") (pinfunction "2_2") (pintype "passive"))
      (node (ref "R61") (pin "2") (pinfunction "2_2") (pintype "passive"))
      (node (ref "R62") (pin "2") (pinfunction "2_2") (pintype "passive"))
      (node (ref "X2") (pin "4") (pinfunction "VDD_4") (pintype "passive"))
    )
    (net (code "195") (name "GND") (class "Default")
      (node (ref "C11") (pin "1") (pinfunction "1_1") (pintype "passive"))
      (node (ref "C12") (pin "1") (pinfunction "1_1") (pintype "passive"))
      (node (ref "C13") (pin "1") (pinfunction "1_1") (pintype "passive"))
      (node (ref "C14") (pin "2") (pinfunction "2_2") (pintype "passive"))
      (node (ref "C17") (pin "2") (pinfunction "2_2") (pintype "passive"))
      (node (ref "C18") (pin "1") (pinfunction "1_1") (pintype "passive"))
      (node (ref "C19") (pin "1") (pinfunction "1_1") (pintype "passive"))
      (node (ref "C20") (pin "1") (pinfunction "1_1") (pintype "passive"))
      (node (ref "C21") (pin "1") (pinfunction "1_1") (pintype "passive"))
      (node (ref "C22") (pin "1") (pinfunction "1_1") (pintype "passive"))
      (node (ref "C23") (pin "1") (pinfunction "1_1") (pintype "passive"))
      (node (ref "C24") (pin "1") (pinfunction "1_1") (pintype "passive"))
      (node (ref "C32") (pin "1") (pinfunction "1_1") (pintype "passive"))
      (node (ref "C33") (pin "1") (pinfunction "1_1") (pintype "passive"))
      (node (ref "C35") (pin "1") (pinfunction "1_1") (pintype "passive"))
      (node (ref "C36") (pin "1") (pinfunction "1_1") (pintype "passive"))
      (node (ref "C37") (pin "1") (pinfunction "1_1") (pintype "passive"))
      (node (ref "C39") (pin "1") (pinfunction "1_1") (pintype "passive"))
      (node (ref "C40") (pin "1") (pinfunction "1_1") (pintype "passive"))
      (node (ref "C44") (pin "1") (pinfunction "1_1") (pintype "passive"))
      (node (ref "C47") (pin "1") (pinfunction "1_1") (pintype "passive"))
      (node (ref "C48") (pin "1") (pinfunction "1_1") (pintype "passive"))
      (node (ref "C5") (pin "1") (pinfunction "1_1") (pintype "passive"))
      (node (ref "C54") (pin "2") (pinfunction "2_2") (pintype "passive"))
      (node (ref "C55") (pin "1") (pinfunction "1_1") (pintype "passive"))
      (node (ref "C56") (pin "1") (pinfunction "1_1") (pintype "passive"))
      (node (ref "C57") (pin "1") (pinfunction "1_1") (pintype "passive"))
      (node (ref "C58") (pin "1") (pinfunction "1_1") (pintype "passive"))
      (node (ref "C59") (pin "1") (pinfunction "1_1") (pintype "passive"))
      (node (ref "C8") (pin "2") (pinfunction "2_2") (pintype "passive"))
      (node (ref "R20") (pin "1") (pinfunction "1_1") (pintype "passive"))
      (node (ref "R35") (pin "1") (pinfunction "1_1") (pintype "passive"))
      (node (ref "R45") (pin "1") (pinfunction "1_1") (pintype "passive"))
      (node (ref "U5") (pin "F10") (pinfunction "VSS2_F10") (pintype "passive"))
      (node (ref "U5") (pin "F2") (pinfunction "VSS13-VSS18_F2") (pintype "passive"))
      (node (ref "U5") (pin "F6") (pinfunction "VSS3_F6") (pintype "passive"))
      (node (ref "U5") (pin "F7") (pinfunction "VSS11_F7") (pintype "passive"))
      (node (ref "U5") (pin "F8") (pinfunction "VSS10_F8") (pintype "passive"))
      (node (ref "U5") (pin "F9") (pinfunction "VSS15_F9") (pintype "passive"))
      (node (ref "U5") (pin "G10") (pinfunction "VSS9_G10") (pintype "passive"))
      (node (ref "U5") (pin "G6") (pinfunction "VSS17_G6") (pintype "passive"))
      (node (ref "U5") (pin "H10") (pinfunction "VSS20_H10") (pintype "passive"))
      (node (ref "U5") (pin "H6") (pinfunction "VSS5_H6") (pintype "passive"))
      (node (ref "U5") (pin "J10") (pinfunction "VSS8_J10") (pintype "passive"))
      (node (ref "U5") (pin "J6") (pinfunction "VSS12_J6") (pintype "passive"))
      (node (ref "U5") (pin "K10") (pinfunction "VSS14_K10") (pintype "passive"))
      (node (ref "U5") (pin "K6") (pinfunction "VSS4_K6") (pintype "passive"))
      (node (ref "U5") (pin "K7") (pinfunction "VSS6_K7") (pintype "passive"))
      (node (ref "U5") (pin "K8") (pinfunction "VSS7_K8") (pintype "passive"))
      (node (ref "U5") (pin "K9") (pinfunction "VSS1_K9") (pintype "passive"))
      (node (ref "U5") (pin "L6") (pinfunction "VSS19_L6") (pintype "passive"))
      (node (ref "U5") (pin "M1") (pinfunction "VSSA_M1") (pintype "passive"))
      (node (ref "U5") (pin "N1") (pinfunction "VREF-_N1") (pintype "passive"))
      (node (ref "X2") (pin "2") (pinfunction "GND_2") (pintype "passive"))
    )
    (net (code "196") (name "Net-(C12-Pad2)") (class "Default")
      (node (ref "C12") (pin "2") (pinfunction "2_2") (pintype "passive"))
      (node (ref "R31") (pin "1") (pinfunction "1_1") (pintype "passive"))
      (node (ref "X3") (pin "2") (pinfunction "2_2") (pintype "passive"))
    )
    (net (code "197") (name "Net-(C13-Pad2)") (class "Default")
      (node (ref "C13") (pin "2") (pinfunction "2_2") (pintype "passive"))
      (node (ref "R32") (pin "1") (pinfunction "1_1") (pintype "passive"))
      (node (ref "X3") (pin "1") (pinfunction "1_1") (pintype "passive"))
    )
    (net (code "198") (name "Net-(R29-Pad2)") (class "Default")
      (node (ref "R29") (pin "2") (pinfunction "2_2") (pintype "passive"))
      (node (ref "TP1") (pin "1") (pinfunction "1_1") (pintype "passive"))
    )
    (net (code "199") (name "Net-(R33-Pad2)") (class "Default")
      (node (ref "R33") (pin "2") (pinfunction "2_2") (pintype "passive"))
      (node (ref "TP2") (pin "1") (pinfunction "1_1") (pintype "passive"))
    )
    (net (code "200") (name "Net-(U5A-PB2)") (class "Default")
      (node (ref "R44") (pin "2") (pinfunction "2_2") (pintype "passive"))
      (node (ref "U5") (pin "M5") (pinfunction "PB2_M5") (pintype "passive"))
    )
    (net (code "201") (name "Net-(U5A-PDR_ON)") (class "Default")
      (node (ref "R35") (pin "2") (pinfunction "2_2") (pintype "passive"))
      (node (ref "R38") (pin "2") (pinfunction "2_2") (pintype "passive"))
      (node (ref "U5") (pin "E5") (pinfunction "PDR_ON_E5") (pintype "passive"))
    )
    (net (code "202") (name "Net-(U5C-BYPASS-REG)") (class "Default")
      (node (ref "R20") (pin "2") (pinfunction "2_2") (pintype "passive"))
      (node (ref "U5") (pin "L5") (pinfunction "BYPASS-REG_L5") (pintype "passive"))
    )
    (net (code "203") (name "Net-(U5C-VCAP1)") (class "Default")
      (node (ref "C47") (pin "2") (pinfunction "2_2") (pintype "passive"))
      (node (ref "U5") (pin "L11") (pinfunction "VCAP1_L11") (pintype "passive"))
    )
    (net (code "204") (name "Net-(U5C-VCAP2)") (class "Default")
      (node (ref "C48") (pin "2") (pinfunction "2_2") (pintype "passive"))
      (node (ref "U5") (pin "E11") (pinfunction "VCAP2_E11") (pintype "passive"))
    )
    (net (code "205") (name "Net-(X2-EN)") (class "Default")
      (node (ref "R5") (pin "2") (pinfunction "2_2") (pintype "passive"))
      (node (ref "X2") (pin "1") (pinfunction "EN_1") (pintype "passive"))
    )
    (net (code "206") (name "VDD") (class "Default")
      (node (ref "C14") (pin "1") (pinfunction "1_1") (pintype "passive"))
      (node (ref "C18") (pin "2") (pinfunction "2_2") (pintype "passive"))
      (node (ref "C19") (pin "2") (pinfunction "2_2") (pintype "passive"))
      (node (ref "C20") (pin "2") (pinfunction "2_2") (pintype "passive"))
      (node (ref "C21") (pin "2") (pinfunction "2_2") (pintype "passive"))
      (node (ref "C22") (pin "2") (pinfunction "2_2") (pintype "passive"))
      (node (ref "C23") (pin "2") (pinfunction "2_2") (pintype "passive"))
      (node (ref "C32") (pin "2") (pinfunction "2_2") (pintype "passive"))
      (node (ref "C33") (pin "2") (pinfunction "2_2") (pintype "passive"))
      (node (ref "C35") (pin "2") (pinfunction "2_2") (pintype "passive"))
      (node (ref "C36") (pin "2") (pinfunction "2_2") (pintype "passive"))
      (node (ref "C37") (pin "2") (pinfunction "2_2") (pintype "passive"))
      (node (ref "C39") (pin "2") (pinfunction "2_2") (pintype "passive"))
      (node (ref "C40") (pin "2") (pinfunction "2_2") (pintype "passive"))
      (node (ref "C44") (pin "2") (pinfunction "2_2") (pintype "passive"))
      (node (ref "C54") (pin "1") (pinfunction "1_1") (pintype "passive"))
      (node (ref "C55") (pin "2") (pinfunction "2_2") (pintype "passive"))
      (node (ref "C56") (pin "2") (pinfunction "2_2") (pintype "passive"))
      (node (ref "C57") (pin "2") (pinfunction "2_2") (pintype "passive"))
      (node (ref "C58") (pin "2") (pinfunction "2_2") (pintype "passive"))
      (node (ref "C59") (pin "2") (pinfunction "2_2") (pintype "passive"))
      (node (ref "L1") (pin "1") (pinfunction "1_1") (pintype "passive"))
      (node (ref "R21") (pin "1") (pinfunction "1_1") (pintype "passive"))
      (node (ref "U5") (pin "C1") (pinfunction "VBAT_C1") (pintype "passive"))
      (node (ref "U5") (pin "E10") (pinfunction "VDD15_E10") (pintype "passive"))
      (node (ref "U5") (pin "E7") (pinfunction "VDD3_E7") (pintype "passive"))
      (node (ref "U5") (pin "E8") (pinfunction "VDD11_E8") (pintype "passive"))
      (node (ref "U5") (pin "E9") (pinfunction "VDD10_E9") (pintype "passive"))
      (node (ref "U5") (pin "F11") (pinfunction "VDD2_F11") (pintype "passive"))
      (node (ref "U5") (pin "F4") (pinfunction "VDD13_F4") (pintype "passive"))
      (node (ref "U5") (pin "F5") (pinfunction "VDD17_F5") (pintype "passive"))
      (node (ref "U5") (pin "G11") (pinfunction "VDD_USB33_G11") (pintype "passive"))
      (node (ref "U5") (pin "G5") (pinfunction "VDD18_G5") (pintype "passive"))
      (node (ref "U5") (pin "H11") (pinfunction "VDD20_H11") (pintype "passive"))
      (node (ref "U5") (pin "H5") (pinfunction "VDD5_H5") (pintype "passive"))
      (node (ref "U5") (pin "J11") (pinfunction "VDD8_J11") (pintype "passive"))
      (node (ref "U5") (pin "J5") (pinfunction "VDD12_J5") (pintype "passive"))
      (node (ref "U5") (pin "K11") (pinfunction "VDD14_K11") (pintype "passive"))
      (node (ref "U5") (pin "K5") (pinfunction "VDD4_K5") (pintype "passive"))
      (node (ref "U5") (pin "L10") (pinfunction "VDD1_L10") (pintype "passive"))
      (node (ref "U5") (pin "L7") (pinfunction "VDD19_L7") (pintype "passive"))
      (node (ref "U5") (pin "L8") (pinfunction "VDD6_L8") (pintype "passive"))
      (node (ref "U5") (pin "L9") (pinfunction "VDD7_L9") (pintype "passive"))
    )
    (net (code "207") (name "VDDA") (class "Default")
      (node (ref "C11") (pin "2") (pinfunction "2_2") (pintype "passive"))
      (node (ref "C8") (pin "1") (pinfunction "1_1") (pintype "passive"))
      (node (ref "L1") (pin "2") (pinfunction "2_2") (pintype "passive"))
      (node (ref "R28") (pin "1") (pinfunction "1_1") (pintype "passive"))
      (node (ref "U5") (pin "R1") (pinfunction "VDDA_R1") (pintype "passive"))
    )
    (net (code "208") (name "VREF+") (class "Default")
      (node (ref "C17") (pin "1") (pinfunction "1_1") (pintype "passive"))
      (node (ref "C24") (pin "2") (pinfunction "2_2") (pintype "passive"))
      (node (ref "R28") (pin "2") (pinfunction "2_2") (pintype "passive"))
      (node (ref "U5") (pin "P1") (pinfunction "VREF+_P1") (pintype "passive"))
    )
  )
)
